# microstepper.net
KiCad netlist of a schematic drawn in EAGLE
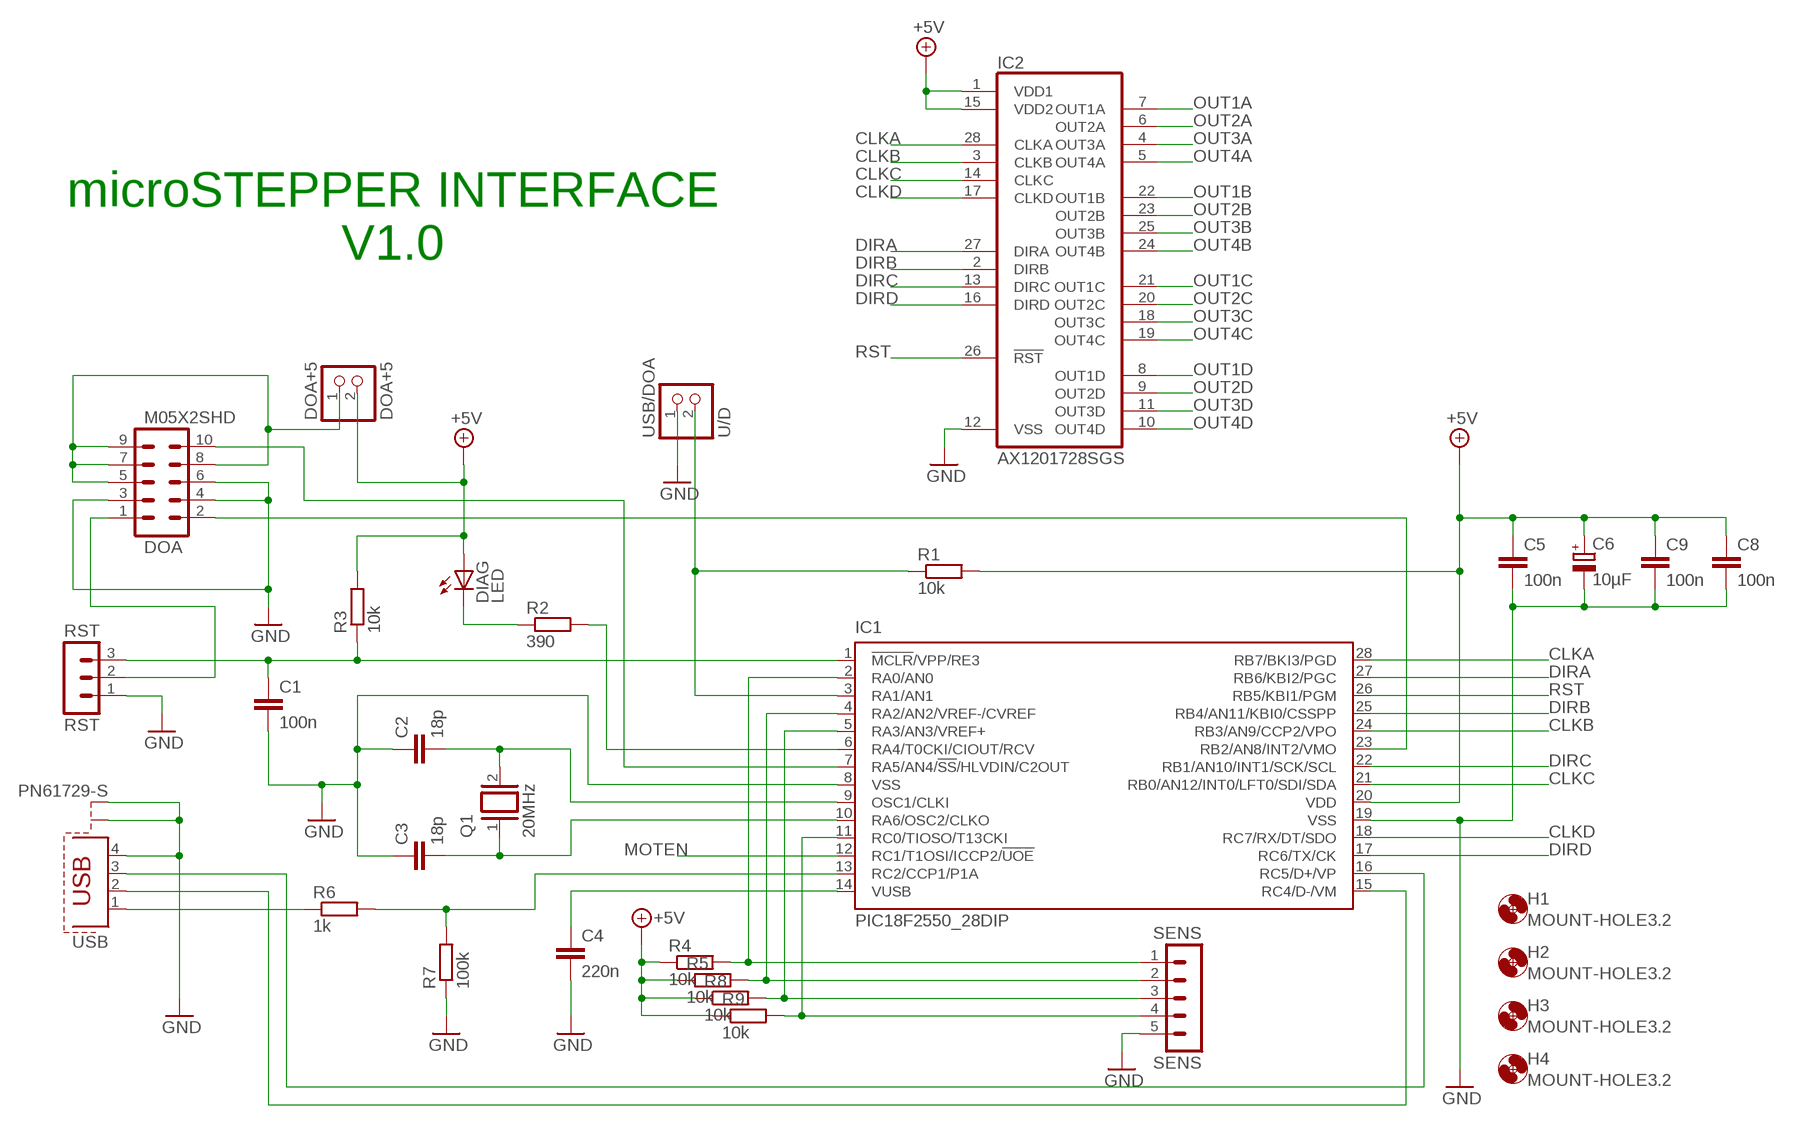
[diagram p0: schematic, sheet 1]
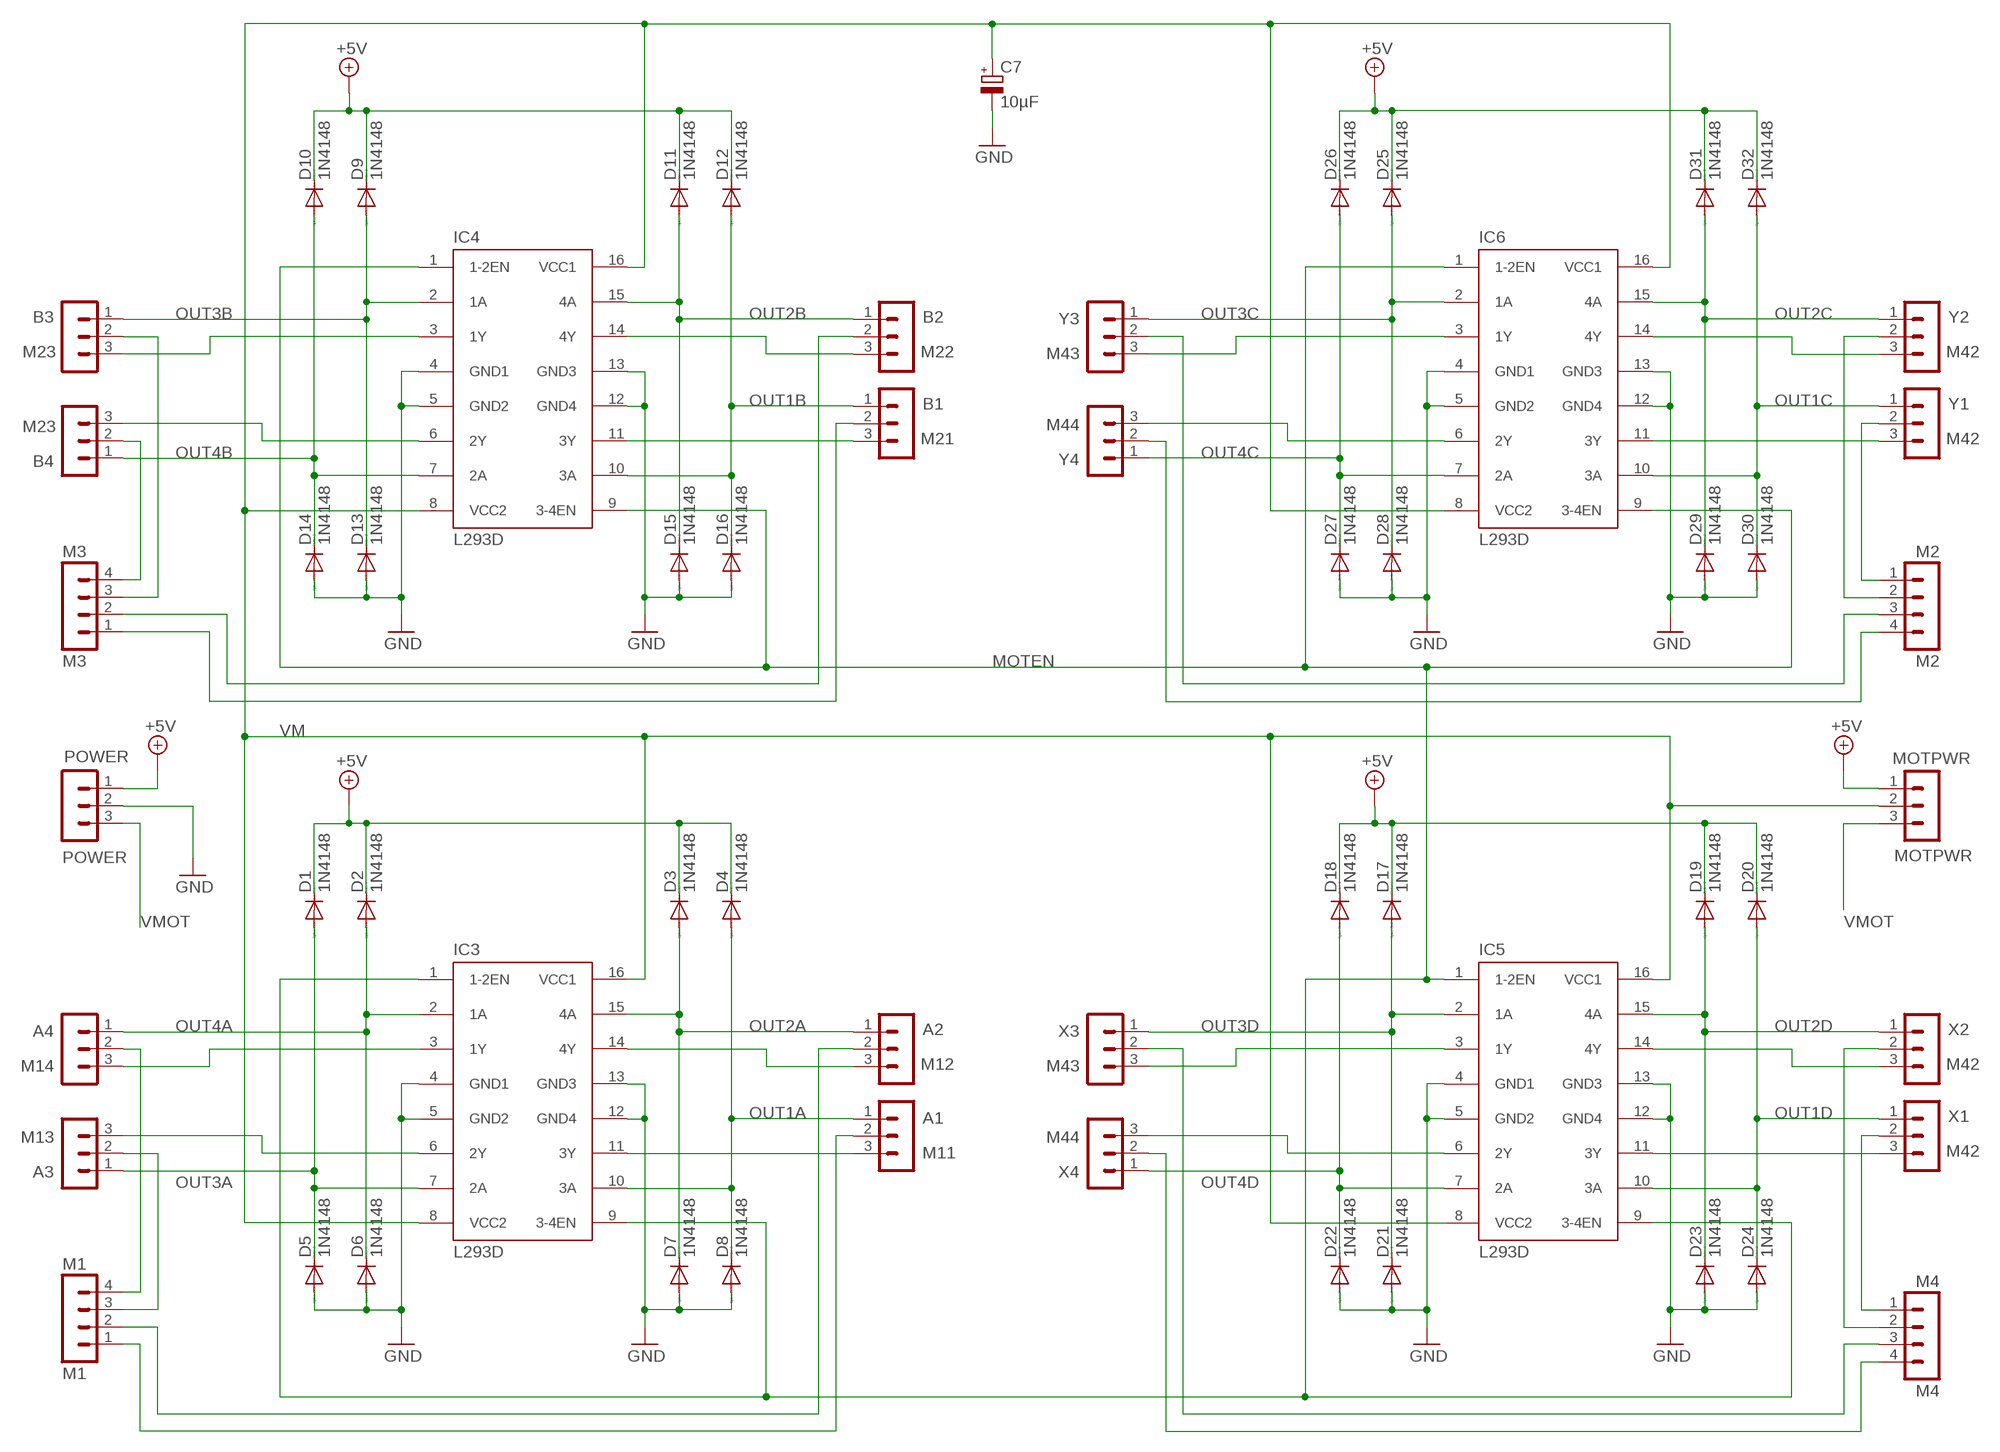
[diagram p1: schematic, sheet 2]
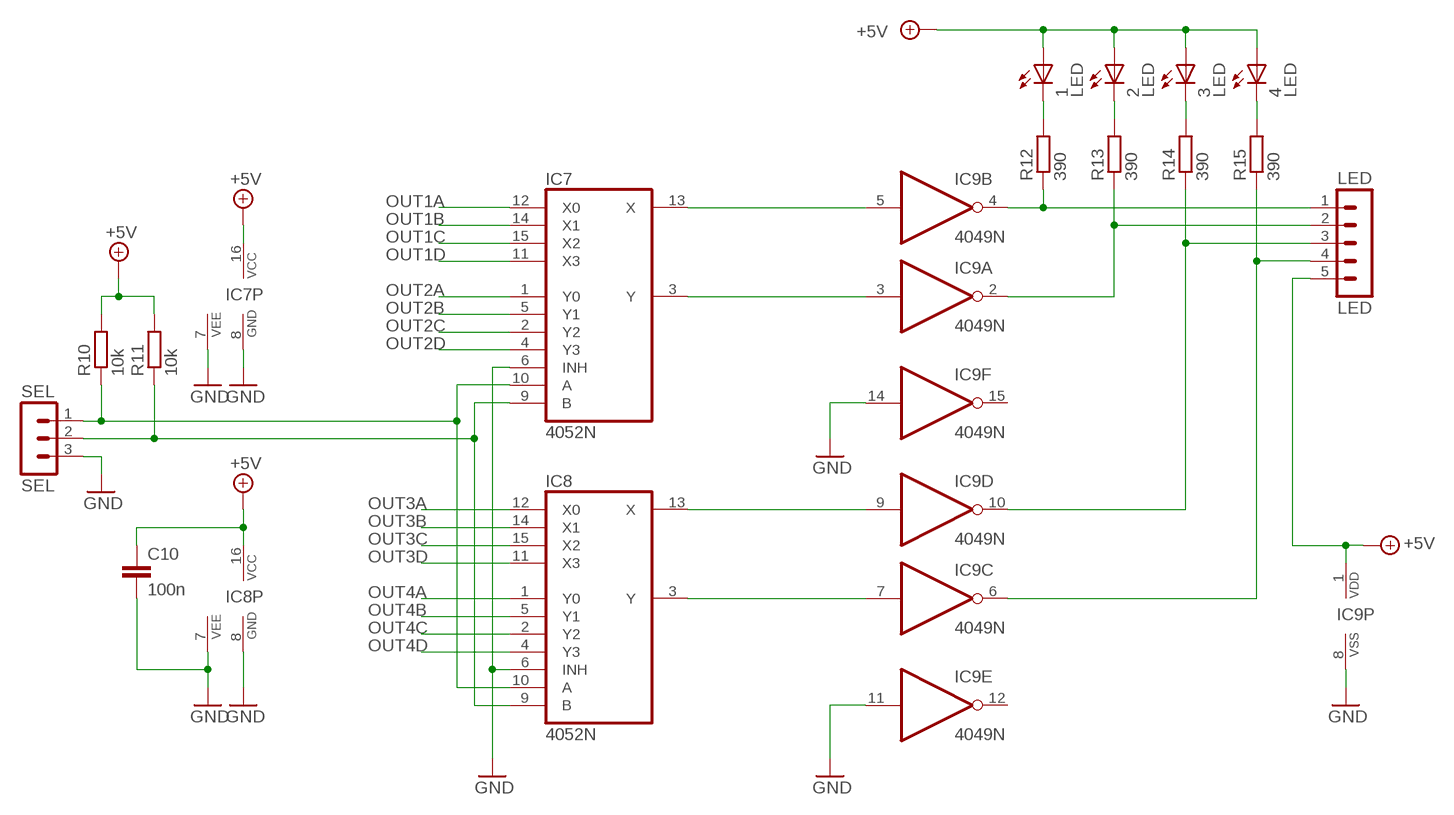
[diagram p2: schematic, sheet 3]

(export (version "E")
  (design (tool "Eeschema 10.0.6"))
  (components
    (comp (ref "C1")
      (value "100n")
      (footprint "eagle-import:C025-025X050")
      (libsource (lib "eagle-import") (part "C-EU025-025X050"))
    )
    (comp (ref "C2")
      (value "18p")
      (footprint "eagle-import:C025-025X050")
      (libsource (lib "eagle-import") (part "C-EU025-025X050"))
    )
    (comp (ref "C3")
      (value "18p")
      (footprint "eagle-import:C025-025X050")
      (libsource (lib "eagle-import") (part "C-EU025-025X050"))
    )
    (comp (ref "C4")
      (value "220n")
      (footprint "eagle-import:C5B3")
      (libsource (lib "eagle-import") (part "C5/3"))
    )
    (comp (ref "C5")
      (value "100n")
      (footprint "eagle-import:C025-025X050")
      (libsource (lib "eagle-import") (part "C-EU025-025X050"))
    )
    (comp (ref "C6")
      (value "10µF")
      (footprint "eagle-import:E2,5-5")
      (libsource (lib "eagle-import") (part "CPOL-EUE2.5-5"))
    )
    (comp (ref "C8")
      (value "100n")
      (footprint "eagle-import:C025-025X050")
      (libsource (lib "eagle-import") (part "C-EU025-025X050"))
    )
    (comp (ref "C9")
      (value "100n")
      (footprint "eagle-import:C025-025X050")
      (libsource (lib "eagle-import") (part "C-EU025-025X050"))
    )
    (comp (ref "DIAG")
      (value "LED")
      (footprint "eagle-import:LED3MM")
      (libsource (lib "eagle-import") (part "LED3MM"))
    )
    (comp (ref "DOA")
      (value "M05X2SHD")
      (footprint "eagle-import:2X5-SHROUDED")
      (libsource (lib "eagle-import") (part "M05X2SHD"))
    )
    (comp (ref "DOA+5")
      (value "DOA+5")
      (footprint "eagle-import:1X02")
      (libsource (lib "eagle-import") (part "PINHD-1X2"))
    )
    (comp (ref "H1")
      (value "MOUNT-HOLE3.2")
      (footprint "eagle-import:3,2")
      (libsource (lib "eagle-import") (part "MOUNT-HOLE3.2"))
    )
    (comp (ref "H2")
      (value "MOUNT-HOLE3.2")
      (footprint "eagle-import:3,2")
      (libsource (lib "eagle-import") (part "MOUNT-HOLE3.2"))
    )
    (comp (ref "H3")
      (value "MOUNT-HOLE3.2")
      (footprint "eagle-import:3,2")
      (libsource (lib "eagle-import") (part "MOUNT-HOLE3.2"))
    )
    (comp (ref "H4")
      (value "MOUNT-HOLE3.2")
      (footprint "eagle-import:3,2")
      (libsource (lib "eagle-import") (part "MOUNT-HOLE3.2"))
    )
    (comp (ref "IC1")
      (value "PIC18F2550_28DIP")
      (footprint "eagle-import:DIL28-3")
      (fields (field (name "MF") "MICROCHIP") (field (name "MPN") "PIC18F2550-I/SP"))
      (libsource (lib "eagle-import") (part "PIC18F2_28DIP550"))
    )
    (comp (ref "IC2")
      (value "AX1201728SGS")
      (footprint "eagle-import:SOP-28")
      (libsource (lib "eagle-import") (part "AX1201728SGS"))
    )
    (comp (ref "Q1")
      (value "20MHz")
      (footprint "eagle-import:QS")
      (libsource (lib "eagle-import") (part "XTAL/S"))
    )
    (comp (ref "R1")
      (value "10k")
      (footprint "eagle-import:0204_7")
      (libsource (lib "eagle-import") (part "R-EU_0204/7"))
    )
    (comp (ref "R2")
      (value "390")
      (footprint "eagle-import:0204_7")
      (libsource (lib "eagle-import") (part "R-EU_0204/7"))
    )
    (comp (ref "R3")
      (value "10k")
      (footprint "eagle-import:0204_7")
      (libsource (lib "eagle-import") (part "R-EU_0204/7"))
    )
    (comp (ref "R4")
      (value "10k")
      (footprint "eagle-import:0204_7")
      (libsource (lib "eagle-import") (part "R-EU_0204/7"))
    )
    (comp (ref "R5")
      (value "10k")
      (footprint "eagle-import:0204_7")
      (libsource (lib "eagle-import") (part "R-EU_0204/7"))
    )
    (comp (ref "R6")
      (value "1k")
      (footprint "eagle-import:0204_7")
      (libsource (lib "eagle-import") (part "R-EU_0204/7"))
    )
    (comp (ref "R7")
      (value "100k")
      (footprint "eagle-import:0204_7")
      (libsource (lib "eagle-import") (part "R-EU_0204/7"))
    )
    (comp (ref "R8")
      (value "10k")
      (footprint "eagle-import:0204_7")
      (libsource (lib "eagle-import") (part "R-EU_0204/7"))
    )
    (comp (ref "R9")
      (value "10k")
      (footprint "eagle-import:0204_7")
      (libsource (lib "eagle-import") (part "R-EU_0204/7"))
    )
    (comp (ref "RST")
      (value "RST")
      (footprint "eagle-import:MA03-1")
      (libsource (lib "eagle-import") (part "MA03-1"))
    )
    (comp (ref "SENS")
      (value "SENS")
      (footprint "eagle-import:MA05-1")
      (libsource (lib "eagle-import") (part "MA05-1"))
    )
    (comp (ref "USB")
      (value "PN61729-S")
      (footprint "eagle-import:PN61729-S")
      (libsource (lib "eagle-import") (part "PN61729-S"))
    )
    (comp (ref "USB/DOA")
      (value "U/D")
      (footprint "eagle-import:1X02")
      (libsource (lib "eagle-import") (part "PINHD-1X2"))
    )
    (comp (ref "1")
      (value "LED")
      (footprint "eagle-import:LED3MM")
      (libsource (lib "eagle-import") (part "LED3MM"))
    )
    (comp (ref "2")
      (value "LED")
      (footprint "eagle-import:LED3MM")
      (libsource (lib "eagle-import") (part "LED3MM"))
    )
    (comp (ref "3")
      (value "LED")
      (footprint "eagle-import:LED3MM")
      (libsource (lib "eagle-import") (part "LED3MM"))
    )
    (comp (ref "4")
      (value "LED")
      (footprint "eagle-import:LED3MM")
      (libsource (lib "eagle-import") (part "LED3MM"))
    )
    (comp (ref "C10")
      (value "100n")
      (footprint "eagle-import:C025-025X050")
      (libsource (lib "eagle-import") (part "C-EU025-025X050"))
    )
    (comp (ref "IC7")
      (value "4052N")
      (footprint "eagle-import:DIL16")
      (libsource (lib "eagle-import") (part "4052N"))
    )
    (comp (ref "IC8")
      (value "4052N")
      (footprint "eagle-import:DIL16")
      (libsource (lib "eagle-import") (part "4052N"))
    )
    (comp (ref "IC9")
      (value "4049N")
      (footprint "eagle-import:DIL16")
      (libsource (lib "eagle-import") (part "4049N"))
    )
    (comp (ref "LED")
      (value "LED")
      (footprint "eagle-import:MA05-1")
      (libsource (lib "eagle-import") (part "MA05-1"))
    )
    (comp (ref "R10")
      (value "10k")
      (footprint "eagle-import:0204_7")
      (libsource (lib "eagle-import") (part "R-EU_0204/7"))
    )
    (comp (ref "R11")
      (value "10k")
      (footprint "eagle-import:0204_7")
      (libsource (lib "eagle-import") (part "R-EU_0204/7"))
    )
    (comp (ref "R12")
      (value "390")
      (footprint "eagle-import:0204_7")
      (libsource (lib "eagle-import") (part "R-EU_0204/7"))
    )
    (comp (ref "R13")
      (value "390")
      (footprint "eagle-import:0204_7")
      (libsource (lib "eagle-import") (part "R-EU_0204/7"))
    )
    (comp (ref "R14")
      (value "390")
      (footprint "eagle-import:0204_7")
      (libsource (lib "eagle-import") (part "R-EU_0204/7"))
    )
    (comp (ref "R15")
      (value "390")
      (footprint "eagle-import:0204_7")
      (libsource (lib "eagle-import") (part "R-EU_0204/7"))
    )
    (comp (ref "SEL")
      (value "SEL")
      (footprint "eagle-import:MA03-1")
      (libsource (lib "eagle-import") (part "MA03-1"))
    )
    (comp (ref "A1")
      (value "M11")
      (footprint "eagle-import:MA03-1")
      (libsource (lib "eagle-import") (part "MA03-1"))
    )
    (comp (ref "A2")
      (value "M12")
      (footprint "eagle-import:MA03-1")
      (libsource (lib "eagle-import") (part "MA03-1"))
    )
    (comp (ref "A3")
      (value "M13")
      (footprint "eagle-import:MA03-1")
      (libsource (lib "eagle-import") (part "MA03-1"))
    )
    (comp (ref "A4")
      (value "M14")
      (footprint "eagle-import:MA03-1")
      (libsource (lib "eagle-import") (part "MA03-1"))
    )
    (comp (ref "B1")
      (value "M21")
      (footprint "eagle-import:MA03-1")
      (libsource (lib "eagle-import") (part "MA03-1"))
    )
    (comp (ref "B2")
      (value "M22")
      (footprint "eagle-import:MA03-1")
      (libsource (lib "eagle-import") (part "MA03-1"))
    )
    (comp (ref "B3")
      (value "M23")
      (footprint "eagle-import:MA03-1")
      (libsource (lib "eagle-import") (part "MA03-1"))
    )
    (comp (ref "B4")
      (value "M23")
      (footprint "eagle-import:MA03-1")
      (libsource (lib "eagle-import") (part "MA03-1"))
    )
    (comp (ref "C7")
      (value "10µF")
      (footprint "eagle-import:E2,5-5")
      (libsource (lib "eagle-import") (part "CPOL-EUE2.5-5"))
    )
    (comp (ref "D1")
      (value "1N4148")
      (footprint "eagle-import:DO35-7")
      (libsource (lib "eagle-import") (part "1N4148DO35-7"))
    )
    (comp (ref "D2")
      (value "1N4148")
      (footprint "eagle-import:DO35-7")
      (libsource (lib "eagle-import") (part "1N4148DO35-7"))
    )
    (comp (ref "D3")
      (value "1N4148")
      (footprint "eagle-import:DO35-7")
      (libsource (lib "eagle-import") (part "1N4148DO35-7"))
    )
    (comp (ref "D4")
      (value "1N4148")
      (footprint "eagle-import:DO35-7")
      (libsource (lib "eagle-import") (part "1N4148DO35-7"))
    )
    (comp (ref "D5")
      (value "1N4148")
      (footprint "eagle-import:DO35-7")
      (libsource (lib "eagle-import") (part "1N4148DO35-7"))
    )
    (comp (ref "D6")
      (value "1N4148")
      (footprint "eagle-import:DO35-7")
      (libsource (lib "eagle-import") (part "1N4148DO35-7"))
    )
    (comp (ref "D7")
      (value "1N4148")
      (footprint "eagle-import:DO35-7")
      (libsource (lib "eagle-import") (part "1N4148DO35-7"))
    )
    (comp (ref "D8")
      (value "1N4148")
      (footprint "eagle-import:DO35-7")
      (libsource (lib "eagle-import") (part "1N4148DO35-7"))
    )
    (comp (ref "D9")
      (value "1N4148")
      (footprint "eagle-import:DO35-7")
      (libsource (lib "eagle-import") (part "1N4148DO35-7"))
    )
    (comp (ref "D10")
      (value "1N4148")
      (footprint "eagle-import:DO35-7")
      (libsource (lib "eagle-import") (part "1N4148DO35-7"))
    )
    (comp (ref "D11")
      (value "1N4148")
      (footprint "eagle-import:DO35-7")
      (libsource (lib "eagle-import") (part "1N4148DO35-7"))
    )
    (comp (ref "D12")
      (value "1N4148")
      (footprint "eagle-import:DO35-7")
      (libsource (lib "eagle-import") (part "1N4148DO35-7"))
    )
    (comp (ref "D13")
      (value "1N4148")
      (footprint "eagle-import:DO35-7")
      (libsource (lib "eagle-import") (part "1N4148DO35-7"))
    )
    (comp (ref "D14")
      (value "1N4148")
      (footprint "eagle-import:DO35-7")
      (libsource (lib "eagle-import") (part "1N4148DO35-7"))
    )
    (comp (ref "D15")
      (value "1N4148")
      (footprint "eagle-import:DO35-7")
      (libsource (lib "eagle-import") (part "1N4148DO35-7"))
    )
    (comp (ref "D16")
      (value "1N4148")
      (footprint "eagle-import:DO35-7")
      (libsource (lib "eagle-import") (part "1N4148DO35-7"))
    )
    (comp (ref "D17")
      (value "1N4148")
      (footprint "eagle-import:DO35-7")
      (libsource (lib "eagle-import") (part "1N4148DO35-7"))
    )
    (comp (ref "D18")
      (value "1N4148")
      (footprint "eagle-import:DO35-7")
      (libsource (lib "eagle-import") (part "1N4148DO35-7"))
    )
    (comp (ref "D19")
      (value "1N4148")
      (footprint "eagle-import:DO35-7")
      (libsource (lib "eagle-import") (part "1N4148DO35-7"))
    )
    (comp (ref "D20")
      (value "1N4148")
      (footprint "eagle-import:DO35-7")
      (libsource (lib "eagle-import") (part "1N4148DO35-7"))
    )
    (comp (ref "D21")
      (value "1N4148")
      (footprint "eagle-import:DO35-7")
      (libsource (lib "eagle-import") (part "1N4148DO35-7"))
    )
    (comp (ref "D22")
      (value "1N4148")
      (footprint "eagle-import:DO35-7")
      (libsource (lib "eagle-import") (part "1N4148DO35-7"))
    )
    (comp (ref "D23")
      (value "1N4148")
      (footprint "eagle-import:DO35-7")
      (libsource (lib "eagle-import") (part "1N4148DO35-7"))
    )
    (comp (ref "D24")
      (value "1N4148")
      (footprint "eagle-import:DO35-7")
      (libsource (lib "eagle-import") (part "1N4148DO35-7"))
    )
    (comp (ref "D25")
      (value "1N4148")
      (footprint "eagle-import:DO35-7")
      (libsource (lib "eagle-import") (part "1N4148DO35-7"))
    )
    (comp (ref "D26")
      (value "1N4148")
      (footprint "eagle-import:DO35-7")
      (libsource (lib "eagle-import") (part "1N4148DO35-7"))
    )
    (comp (ref "D27")
      (value "1N4148")
      (footprint "eagle-import:DO35-7")
      (libsource (lib "eagle-import") (part "1N4148DO35-7"))
    )
    (comp (ref "D28")
      (value "1N4148")
      (footprint "eagle-import:DO35-7")
      (libsource (lib "eagle-import") (part "1N4148DO35-7"))
    )
    (comp (ref "D29")
      (value "1N4148")
      (footprint "eagle-import:DO35-7")
      (libsource (lib "eagle-import") (part "1N4148DO35-7"))
    )
    (comp (ref "D30")
      (value "1N4148")
      (footprint "eagle-import:DO35-7")
      (libsource (lib "eagle-import") (part "1N4148DO35-7"))
    )
    (comp (ref "D31")
      (value "1N4148")
      (footprint "eagle-import:DO35-7")
      (libsource (lib "eagle-import") (part "1N4148DO35-7"))
    )
    (comp (ref "D32")
      (value "1N4148")
      (footprint "eagle-import:DO35-7")
      (libsource (lib "eagle-import") (part "1N4148DO35-7"))
    )
    (comp (ref "IC3")
      (value "L293D")
      (footprint "eagle-import:DIL16")
      (libsource (lib "eagle-import") (part "L293D"))
    )
    (comp (ref "IC4")
      (value "L293D")
      (footprint "eagle-import:DIL16")
      (libsource (lib "eagle-import") (part "L293D"))
    )
    (comp (ref "IC5")
      (value "L293D")
      (footprint "eagle-import:DIL16")
      (libsource (lib "eagle-import") (part "L293D"))
    )
    (comp (ref "IC6")
      (value "L293D")
      (footprint "eagle-import:DIL16")
      (libsource (lib "eagle-import") (part "L293D"))
    )
    (comp (ref "M1")
      (value "M1")
      (footprint "eagle-import:MA04-1")
      (libsource (lib "eagle-import") (part "MA04-1"))
    )
    (comp (ref "M2")
      (value "M2")
      (footprint "eagle-import:MA04-1")
      (libsource (lib "eagle-import") (part "MA04-1"))
    )
    (comp (ref "M3")
      (value "M3")
      (footprint "eagle-import:MA04-1")
      (libsource (lib "eagle-import") (part "MA04-1"))
    )
    (comp (ref "M4")
      (value "M4")
      (footprint "eagle-import:MA04-1")
      (libsource (lib "eagle-import") (part "MA04-1"))
    )
    (comp (ref "MOTPWR")
      (value "MOTPWR")
      (footprint "eagle-import:MA03-1")
      (libsource (lib "eagle-import") (part "MA03-1"))
    )
    (comp (ref "POWER")
      (value "POWER")
      (footprint "eagle-import:MA03-1")
      (libsource (lib "eagle-import") (part "MA03-1"))
    )
    (comp (ref "X1")
      (value "M42")
      (footprint "eagle-import:MA03-1")
      (libsource (lib "eagle-import") (part "MA03-1"))
    )
    (comp (ref "X2")
      (value "M42")
      (footprint "eagle-import:MA03-1")
      (libsource (lib "eagle-import") (part "MA03-1"))
    )
    (comp (ref "X3")
      (value "M43")
      (footprint "eagle-import:MA03-1")
      (libsource (lib "eagle-import") (part "MA03-1"))
    )
    (comp (ref "X4")
      (value "M44")
      (footprint "eagle-import:MA03-1")
      (libsource (lib "eagle-import") (part "MA03-1"))
    )
    (comp (ref "Y1")
      (value "M42")
      (footprint "eagle-import:MA03-1")
      (libsource (lib "eagle-import") (part "MA03-1"))
    )
    (comp (ref "Y2")
      (value "M42")
      (footprint "eagle-import:MA03-1")
      (libsource (lib "eagle-import") (part "MA03-1"))
    )
    (comp (ref "Y3")
      (value "M43")
      (footprint "eagle-import:MA03-1")
      (libsource (lib "eagle-import") (part "MA03-1"))
    )
    (comp (ref "Y4")
      (value "M44")
      (footprint "eagle-import:MA03-1")
      (libsource (lib "eagle-import") (part "MA03-1"))
    )
  )
  (nets
    (net (code "1") (name "+5V") (class "Default")
      (node (ref "1") (pin "A") (pinfunction "A_A") (pintype "passive"))
      (node (ref "2") (pin "A") (pinfunction "A_A") (pintype "passive"))
      (node (ref "3") (pin "A") (pinfunction "A_A") (pintype "passive"))
      (node (ref "4") (pin "A") (pinfunction "A_A") (pintype "passive"))
      (node (ref "C10") (pin "1") (pinfunction "1_1") (pintype "passive"))
      (node (ref "C5") (pin "1") (pinfunction "1_1") (pintype "passive"))
      (node (ref "C6") (pin "+") (pinfunction "+_+") (pintype "passive"))
      (node (ref "C8") (pin "1") (pinfunction "1_1") (pintype "passive"))
      (node (ref "C9") (pin "1") (pinfunction "1_1") (pintype "passive"))
      (node (ref "D1") (pin "C") (pinfunction "C_C") (pintype "passive"))
      (node (ref "D10") (pin "C") (pinfunction "C_C") (pintype "passive"))
      (node (ref "D11") (pin "C") (pinfunction "C_C") (pintype "passive"))
      (node (ref "D12") (pin "C") (pinfunction "C_C") (pintype "passive"))
      (node (ref "D17") (pin "C") (pinfunction "C_C") (pintype "passive"))
      (node (ref "D18") (pin "C") (pinfunction "C_C") (pintype "passive"))
      (node (ref "D19") (pin "C") (pinfunction "C_C") (pintype "passive"))
      (node (ref "D2") (pin "C") (pinfunction "C_C") (pintype "passive"))
      (node (ref "D20") (pin "C") (pinfunction "C_C") (pintype "passive"))
      (node (ref "D25") (pin "C") (pinfunction "C_C") (pintype "passive"))
      (node (ref "D26") (pin "C") (pinfunction "C_C") (pintype "passive"))
      (node (ref "D3") (pin "C") (pinfunction "C_C") (pintype "passive"))
      (node (ref "D31") (pin "C") (pinfunction "C_C") (pintype "passive"))
      (node (ref "D32") (pin "C") (pinfunction "C_C") (pintype "passive"))
      (node (ref "D4") (pin "C") (pinfunction "C_C") (pintype "passive"))
      (node (ref "D9") (pin "C") (pinfunction "C_C") (pintype "passive"))
      (node (ref "DIAG") (pin "A") (pinfunction "A_A") (pintype "passive"))
      (node (ref "DOA+5") (pin "2") (pinfunction "2_2") (pintype "passive"))
      (node (ref "IC1") (pin "20") (pinfunction "VDD_20") (pintype "power_in"))
      (node (ref "IC2") (pin "1") (pinfunction "VDD1_1") (pintype "power_in"))
      (node (ref "IC2") (pin "15") (pinfunction "VDD2_15") (pintype "power_in"))
      (node (ref "IC7") (pin "16") (pinfunction "VCC_16") (pintype "power_in"))
      (node (ref "IC8") (pin "16") (pinfunction "VCC_16") (pintype "power_in"))
      (node (ref "IC9") (pin "1") (pinfunction "VDD_1") (pintype "power_in"))
      (node (ref "LED") (pin "5") (pinfunction "5_5") (pintype "passive"))
      (node (ref "MOTPWR") (pin "1") (pinfunction "1_1") (pintype "passive"))
      (node (ref "POWER") (pin "1") (pinfunction "1_1") (pintype "passive"))
      (node (ref "R1") (pin "2") (pinfunction "2_2") (pintype "passive"))
      (node (ref "R10") (pin "2") (pinfunction "2_2") (pintype "passive"))
      (node (ref "R11") (pin "2") (pinfunction "2_2") (pintype "passive"))
      (node (ref "R3") (pin "2") (pinfunction "2_2") (pintype "passive"))
      (node (ref "R4") (pin "1") (pinfunction "1_1") (pintype "passive"))
      (node (ref "R5") (pin "1") (pinfunction "1_1") (pintype "passive"))
      (node (ref "R8") (pin "1") (pinfunction "1_1") (pintype "passive"))
      (node (ref "R9") (pin "1") (pinfunction "1_1") (pintype "passive"))
    )
    (net (code "2") (name "CLKA") (class "Default")
      (node (ref "IC1") (pin "28") (pinfunction "RB7/BKI3/PGD_28") (pintype "bidirectional"))
      (node (ref "IC2") (pin "28") (pinfunction "CLKA_28") (pintype "input"))
    )
    (net (code "3") (name "CLKB") (class "Default")
      (node (ref "IC1") (pin "24") (pinfunction "RB3/AN9/CCP2/VPO_24") (pintype "bidirectional"))
      (node (ref "IC2") (pin "3") (pinfunction "CLKB_3") (pintype "input"))
    )
    (net (code "4") (name "CLKC") (class "Default")
      (node (ref "IC1") (pin "21") (pinfunction "RB0/AN12/INT0/LFT0/SDI/SDA_21") (pintype "bidirectional"))
      (node (ref "IC2") (pin "14") (pinfunction "CLKC_14") (pintype "input"))
    )
    (net (code "5") (name "CLKD") (class "Default")
      (node (ref "IC1") (pin "18") (pinfunction "RC7/RX/DT/SDO_18") (pintype "bidirectional"))
      (node (ref "IC2") (pin "17") (pinfunction "CLKD_17") (pintype "input"))
    )
    (net (code "6") (name "DIRA") (class "Default")
      (node (ref "IC1") (pin "27") (pinfunction "RB6/KBI2/PGC_27") (pintype "bidirectional"))
      (node (ref "IC2") (pin "27") (pinfunction "DIRA_27") (pintype "input"))
    )
    (net (code "7") (name "DIRB") (class "Default")
      (node (ref "IC1") (pin "25") (pinfunction "RB4/AN11/KBI0/CSSPP_25") (pintype "bidirectional"))
      (node (ref "IC2") (pin "2") (pinfunction "DIRB_2") (pintype "input"))
    )
    (net (code "8") (name "DIRC") (class "Default")
      (node (ref "IC1") (pin "22") (pinfunction "RB1/AN10/INT1/SCK/SCL_22") (pintype "bidirectional"))
      (node (ref "IC2") (pin "13") (pinfunction "DIRC_13") (pintype "input"))
    )
    (net (code "9") (name "DIRD") (class "Default")
      (node (ref "IC1") (pin "17") (pinfunction "RC6/TX/CK_17") (pintype "bidirectional"))
      (node (ref "IC2") (pin "16") (pinfunction "DIRD_16") (pintype "input"))
    )
    (net (code "10") (name "GND") (class "Default")
      (node (ref "C1") (pin "2") (pinfunction "2_2") (pintype "passive"))
      (node (ref "C10") (pin "2") (pinfunction "2_2") (pintype "passive"))
      (node (ref "C2") (pin "1") (pinfunction "1_1") (pintype "passive"))
      (node (ref "C3") (pin "1") (pinfunction "1_1") (pintype "passive"))
      (node (ref "C4") (pin "2") (pinfunction "2_2") (pintype "passive"))
      (node (ref "C5") (pin "2") (pinfunction "2_2") (pintype "passive"))
      (node (ref "C6") (pin "-") (pinfunction "-_-") (pintype "passive"))
      (node (ref "C7") (pin "-") (pinfunction "-_-") (pintype "passive"))
      (node (ref "C8") (pin "2") (pinfunction "2_2") (pintype "passive"))
      (node (ref "C9") (pin "2") (pinfunction "2_2") (pintype "passive"))
      (node (ref "D13") (pin "A") (pinfunction "A_A") (pintype "passive"))
      (node (ref "D14") (pin "A") (pinfunction "A_A") (pintype "passive"))
      (node (ref "D15") (pin "A") (pinfunction "A_A") (pintype "passive"))
      (node (ref "D16") (pin "A") (pinfunction "A_A") (pintype "passive"))
      (node (ref "D21") (pin "A") (pinfunction "A_A") (pintype "passive"))
      (node (ref "D22") (pin "A") (pinfunction "A_A") (pintype "passive"))
      (node (ref "D23") (pin "A") (pinfunction "A_A") (pintype "passive"))
      (node (ref "D24") (pin "A") (pinfunction "A_A") (pintype "passive"))
      (node (ref "D27") (pin "A") (pinfunction "A_A") (pintype "passive"))
      (node (ref "D28") (pin "A") (pinfunction "A_A") (pintype "passive"))
      (node (ref "D29") (pin "A") (pinfunction "A_A") (pintype "passive"))
      (node (ref "D30") (pin "A") (pinfunction "A_A") (pintype "passive"))
      (node (ref "D5") (pin "A") (pinfunction "A_A") (pintype "passive"))
      (node (ref "D6") (pin "A") (pinfunction "A_A") (pintype "passive"))
      (node (ref "D7") (pin "A") (pinfunction "A_A") (pintype "passive"))
      (node (ref "D8") (pin "A") (pinfunction "A_A") (pintype "passive"))
      (node (ref "DOA") (pin "3") (pinfunction "3_3") (pintype "passive"))
      (node (ref "DOA") (pin "4") (pinfunction "4_4") (pintype "passive"))
      (node (ref "DOA") (pin "6") (pinfunction "6_6") (pintype "passive"))
      (node (ref "IC1") (pin "19") (pinfunction "VSS_19") (pintype "power_in"))
      (node (ref "IC1") (pin "8") (pinfunction "VSS_8") (pintype "power_in"))
      (node (ref "IC2") (pin "12") (pinfunction "VSS_12") (pintype "power_in"))
      (node (ref "IC3") (pin "12") (pinfunction "GND4_12") (pintype "power_in"))
      (node (ref "IC3") (pin "13") (pinfunction "GND3_13") (pintype "power_in"))
      (node (ref "IC3") (pin "4") (pinfunction "GND1_4") (pintype "power_in"))
      (node (ref "IC3") (pin "5") (pinfunction "GND2_5") (pintype "power_in"))
      (node (ref "IC4") (pin "12") (pinfunction "GND4_12") (pintype "power_in"))
      (node (ref "IC4") (pin "13") (pinfunction "GND3_13") (pintype "power_in"))
      (node (ref "IC4") (pin "4") (pinfunction "GND1_4") (pintype "power_in"))
      (node (ref "IC4") (pin "5") (pinfunction "GND2_5") (pintype "power_in"))
      (node (ref "IC5") (pin "12") (pinfunction "GND4_12") (pintype "power_in"))
      (node (ref "IC5") (pin "13") (pinfunction "GND3_13") (pintype "power_in"))
      (node (ref "IC5") (pin "4") (pinfunction "GND1_4") (pintype "power_in"))
      (node (ref "IC5") (pin "5") (pinfunction "GND2_5") (pintype "power_in"))
      (node (ref "IC6") (pin "12") (pinfunction "GND4_12") (pintype "power_in"))
      (node (ref "IC6") (pin "13") (pinfunction "GND3_13") (pintype "power_in"))
      (node (ref "IC6") (pin "4") (pinfunction "GND1_4") (pintype "power_in"))
      (node (ref "IC6") (pin "5") (pinfunction "GND2_5") (pintype "power_in"))
      (node (ref "IC7") (pin "6") (pinfunction "INH_6") (pintype "input"))
      (node (ref "IC7") (pin "7") (pinfunction "VEE_7") (pintype "power_in"))
      (node (ref "IC7") (pin "8") (pinfunction "GND_8") (pintype "power_in"))
      (node (ref "IC8") (pin "6") (pinfunction "INH_6") (pintype "input"))
      (node (ref "IC8") (pin "7") (pinfunction "VEE_7") (pintype "power_in"))
      (node (ref "IC8") (pin "8") (pinfunction "GND_8") (pintype "power_in"))
      (node (ref "IC9") (pin "11") (pinfunction "I_11") (pintype "input"))
      (node (ref "IC9") (pin "14") (pinfunction "I_14") (pintype "input"))
      (node (ref "IC9") (pin "8") (pinfunction "VSS_8") (pintype "power_in"))
      (node (ref "POWER") (pin "2") (pinfunction "2_2") (pintype "passive"))
      (node (ref "R7") (pin "1") (pinfunction "1_1") (pintype "passive"))
      (node (ref "RST") (pin "1") (pinfunction "1_1") (pintype "passive"))
      (node (ref "SEL") (pin "3") (pinfunction "3_3") (pintype "passive"))
      (node (ref "SENS") (pin "5") (pinfunction "5_5") (pintype "passive"))
      (node (ref "USB") (pin "4") (pinfunction "4_4") (pintype "passive"))
      (node (ref "USB") (pin "S1") (pinfunction "S1_S1") (pintype "passive"))
      (node (ref "USB") (pin "S2") (pinfunction "S2_S2") (pintype "passive"))
      (node (ref "USB/DOA") (pin "1") (pinfunction "1_1") (pintype "passive"))
    )
    (net (code "11") (name "MOTEN") (class "Default")
      (node (ref "IC1") (pin "12") (pinfunction "RC1/T1OSI/ICCP2/~{UOE}_12") (pintype "bidirectional"))
      (node (ref "IC3") (pin "1") (pinfunction "1-2EN_1") (pintype "input"))
      (node (ref "IC3") (pin "9") (pinfunction "3-4EN_9") (pintype "input"))
      (node (ref "IC4") (pin "1") (pinfunction "1-2EN_1") (pintype "input"))
      (node (ref "IC4") (pin "9") (pinfunction "3-4EN_9") (pintype "input"))
      (node (ref "IC5") (pin "1") (pinfunction "1-2EN_1") (pintype "input"))
      (node (ref "IC5") (pin "9") (pinfunction "3-4EN_9") (pintype "input"))
      (node (ref "IC6") (pin "1") (pinfunction "1-2EN_1") (pintype "input"))
      (node (ref "IC6") (pin "9") (pinfunction "3-4EN_9") (pintype "input"))
    )
    (net (code "12") (name "Net-(1-C)") (class "Default")
      (node (ref "1") (pin "K") (pinfunction "C_K") (pintype "passive"))
      (node (ref "R12") (pin "2") (pinfunction "2_2") (pintype "passive"))
    )
    (net (code "13") (name "Net-(2-C)") (class "Default")
      (node (ref "2") (pin "K") (pinfunction "C_K") (pintype "passive"))
      (node (ref "R13") (pin "2") (pinfunction "2_2") (pintype "passive"))
    )
    (net (code "14") (name "Net-(3-C)") (class "Default")
      (node (ref "3") (pin "K") (pinfunction "C_K") (pintype "passive"))
      (node (ref "R14") (pin "2") (pinfunction "2_2") (pintype "passive"))
    )
    (net (code "15") (name "Net-(4-C)") (class "Default")
      (node (ref "4") (pin "K") (pinfunction "C_K") (pintype "passive"))
      (node (ref "R15") (pin "2") (pinfunction "2_2") (pintype "passive"))
    )
    (net (code "16") (name "Net-(A1-Pad2)") (class "Default")
      (node (ref "A1") (pin "2") (pinfunction "2_2") (pintype "passive"))
      (node (ref "M1") (pin "1") (pinfunction "1_1") (pintype "passive"))
    )
    (net (code "17") (name "Net-(A2-Pad2)") (class "Default")
      (node (ref "A2") (pin "2") (pinfunction "2_2") (pintype "passive"))
      (node (ref "M1") (pin "2") (pinfunction "2_2") (pintype "passive"))
    )
    (net (code "18") (name "Net-(A3-Pad2)") (class "Default")
      (node (ref "A3") (pin "2") (pinfunction "2_2") (pintype "passive"))
      (node (ref "M1") (pin "3") (pinfunction "3_3") (pintype "passive"))
    )
    (net (code "19") (name "Net-(A4-Pad2)") (class "Default")
      (node (ref "A4") (pin "2") (pinfunction "2_2") (pintype "passive"))
      (node (ref "M1") (pin "4") (pinfunction "4_4") (pintype "passive"))
    )
    (net (code "20") (name "Net-(B1-Pad2)") (class "Default")
      (node (ref "B1") (pin "2") (pinfunction "2_2") (pintype "passive"))
      (node (ref "M3") (pin "1") (pinfunction "1_1") (pintype "passive"))
    )
    (net (code "21") (name "Net-(B2-Pad2)") (class "Default")
      (node (ref "B2") (pin "2") (pinfunction "2_2") (pintype "passive"))
      (node (ref "M3") (pin "2") (pinfunction "2_2") (pintype "passive"))
    )
    (net (code "22") (name "Net-(B3-Pad2)") (class "Default")
      (node (ref "B3") (pin "2") (pinfunction "2_2") (pintype "passive"))
      (node (ref "M3") (pin "3") (pinfunction "3_3") (pintype "passive"))
    )
    (net (code "23") (name "Net-(B4-Pad2)") (class "Default")
      (node (ref "B4") (pin "2") (pinfunction "2_2") (pintype "passive"))
      (node (ref "M3") (pin "4") (pinfunction "4_4") (pintype "passive"))
    )
    (net (code "24") (name "Net-(DIAG-C)") (class "Default")
      (node (ref "DIAG") (pin "K") (pinfunction "C_K") (pintype "passive"))
      (node (ref "R2") (pin "1") (pinfunction "1_1") (pintype "passive"))
    )
    (net (code "25") (name "Net-(DOA+5-Pad1)") (class "Default")
      (node (ref "DOA") (pin "5") (pinfunction "5_5") (pintype "passive"))
      (node (ref "DOA") (pin "7") (pinfunction "7_7") (pintype "passive"))
      (node (ref "DOA") (pin "8") (pinfunction "8_8") (pintype "passive"))
      (node (ref "DOA") (pin "9") (pinfunction "9_9") (pintype "passive"))
      (node (ref "DOA+5") (pin "1") (pinfunction "1_1") (pintype "passive"))
    )
    (net (code "26") (name "Net-(DOA-Pad1)") (class "Default")
      (node (ref "DOA") (pin "1") (pinfunction "1_1") (pintype "passive"))
      (node (ref "RST") (pin "2") (pinfunction "2_2") (pintype "passive"))
    )
    (net (code "27") (name "Net-(IC1-OSC1{slash}CLKI)") (class "Default")
      (node (ref "C2") (pin "2") (pinfunction "2_2") (pintype "passive"))
      (node (ref "IC1") (pin "9") (pinfunction "OSC1/CLKI_9") (pintype "input"))
      (node (ref "Q1") (pin "2") (pinfunction "2_2") (pintype "passive"))
    )
    (net (code "28") (name "Net-(IC1-RA0{slash}AN0)") (class "Default")
      (node (ref "IC1") (pin "2") (pinfunction "RA0/AN0_2") (pintype "bidirectional"))
      (node (ref "R4") (pin "2") (pinfunction "2_2") (pintype "passive"))
      (node (ref "SENS") (pin "1") (pinfunction "1_1") (pintype "passive"))
    )
    (net (code "29") (name "Net-(IC1-RA1{slash}AN1)") (class "Default")
      (node (ref "IC1") (pin "3") (pinfunction "RA1/AN1_3") (pintype "bidirectional"))
      (node (ref "R1") (pin "1") (pinfunction "1_1") (pintype "passive"))
      (node (ref "USB/DOA") (pin "2") (pinfunction "2_2") (pintype "passive"))
    )
    (net (code "30") (name "Net-(IC1-RA2{slash}AN2{slash}VREF-{slash}CVREF)") (class "Default")
      (node (ref "IC1") (pin "4") (pinfunction "RA2/AN2/VREF-/CVREF_4") (pintype "bidirectional"))
      (node (ref "R5") (pin "2") (pinfunction "2_2") (pintype "passive"))
      (node (ref "SENS") (pin "2") (pinfunction "2_2") (pintype "passive"))
    )
    (net (code "31") (name "Net-(IC1-RA3{slash}AN3{slash}VREF+)") (class "Default")
      (node (ref "IC1") (pin "5") (pinfunction "RA3/AN3/VREF+_5") (pintype "bidirectional"))
      (node (ref "R8") (pin "2") (pinfunction "2_2") (pintype "passive"))
      (node (ref "SENS") (pin "3") (pinfunction "3_3") (pintype "passive"))
    )
    (net (code "32") (name "Net-(IC1-RA4{slash}T0CKI{slash}CIOUT{slash}RCV)") (class "Default")
      (node (ref "IC1") (pin "6") (pinfunction "RA4/T0CKI/CIOUT/RCV_6") (pintype "bidirectional"))
      (node (ref "R2") (pin "2") (pinfunction "2_2") (pintype "passive"))
    )
    (net (code "33") (name "Net-(IC1-RA5{slash}AN4{slash}~{SS}{slash}HLVDIN{slash}C2OUT)") (class "Default")
      (node (ref "DOA") (pin "10") (pinfunction "10_10") (pintype "passive"))
      (node (ref "IC1") (pin "7") (pinfunction "RA5/AN4/~{SS}/HLVDIN/C2OUT_7") (pintype "bidirectional"))
    )
    (net (code "34") (name "Net-(IC1-RA6{slash}OSC2{slash}CLKO)") (class "Default")
      (node (ref "C3") (pin "2") (pinfunction "2_2") (pintype "passive"))
      (node (ref "IC1") (pin "10") (pinfunction "RA6/OSC2/CLKO_10") (pintype "output"))
      (node (ref "Q1") (pin "1") (pinfunction "1_1") (pintype "passive"))
    )
    (net (code "35") (name "Net-(IC1-RB2{slash}AN8{slash}INT2{slash}VMO)") (class "Default")
      (node (ref "DOA") (pin "2") (pinfunction "2_2") (pintype "passive"))
      (node (ref "IC1") (pin "23") (pinfunction "RB2/AN8/INT2/VMO_23") (pintype "bidirectional"))
    )
    (net (code "36") (name "Net-(IC1-RC0{slash}TIOSO{slash}T13CKI)") (class "Default")
      (node (ref "IC1") (pin "11") (pinfunction "RC0/TIOSO/T13CKI_11") (pintype "bidirectional"))
      (node (ref "R9") (pin "2") (pinfunction "2_2") (pintype "passive"))
      (node (ref "SENS") (pin "4") (pinfunction "4_4") (pintype "passive"))
    )
    (net (code "37") (name "Net-(IC1-RC2{slash}CCP1{slash}P1A)") (class "Default")
      (node (ref "IC1") (pin "13") (pinfunction "RC2/CCP1/P1A_13") (pintype "bidirectional"))
      (node (ref "R6") (pin "2") (pinfunction "2_2") (pintype "passive"))
      (node (ref "R7") (pin "2") (pinfunction "2_2") (pintype "passive"))
    )
    (net (code "38") (name "Net-(IC1-RC4{slash}D-{slash}VM)") (class "Default")
      (node (ref "IC1") (pin "15") (pinfunction "RC4/D-/VM_15") (pintype "bidirectional"))
      (node (ref "USB") (pin "2") (pinfunction "2_2") (pintype "passive"))
    )
    (net (code "39") (name "Net-(IC1-RC5{slash}D+{slash}VP)") (class "Default")
      (node (ref "IC1") (pin "16") (pinfunction "RC5/D+/VP_16") (pintype "bidirectional"))
      (node (ref "USB") (pin "3") (pinfunction "3_3") (pintype "passive"))
    )
    (net (code "40") (name "Net-(IC1-VUSB)") (class "Default")
      (node (ref "C4") (pin "1") (pinfunction "1_1") (pintype "passive"))
      (node (ref "IC1") (pin "14") (pinfunction "VUSB_14") (pintype "bidirectional"))
    )
    (net (code "41") (name "Net-(IC1-~{MCLR}{slash}VPP{slash}RE3)") (class "Default")
      (node (ref "C1") (pin "1") (pinfunction "1_1") (pintype "passive"))
      (node (ref "IC1") (pin "1") (pinfunction "~{MCLR}/VPP/RE3_1") (pintype "input"))
      (node (ref "R3") (pin "1") (pinfunction "1_1") (pintype "passive"))
      (node (ref "RST") (pin "3") (pinfunction "3_3") (pintype "passive"))
    )
    (net (code "42") (name "Net-(IC3-1Y)") (class "Default")
      (node (ref "A4") (pin "3") (pinfunction "3_3") (pintype "passive"))
      (node (ref "IC3") (pin "3") (pinfunction "1Y_3") (pintype "output"))
    )
    (net (code "43") (name "Net-(IC3-2Y)") (class "Default")
      (node (ref "A3") (pin "3") (pinfunction "3_3") (pintype "passive"))
      (node (ref "IC3") (pin "6") (pinfunction "2Y_6") (pintype "output"))
    )
    (net (code "44") (name "Net-(IC3-3Y)") (class "Default")
      (node (ref "A1") (pin "3") (pinfunction "3_3") (pintype "passive"))
      (node (ref "IC3") (pin "11") (pinfunction "3Y_11") (pintype "output"))
    )
    (net (code "45") (name "Net-(IC3-4Y)") (class "Default")
      (node (ref "A2") (pin "3") (pinfunction "3_3") (pintype "passive"))
      (node (ref "IC3") (pin "14") (pinfunction "4Y_14") (pintype "output"))
    )
    (net (code "46") (name "Net-(IC4-1Y)") (class "Default")
      (node (ref "B3") (pin "3") (pinfunction "3_3") (pintype "passive"))
      (node (ref "IC4") (pin "3") (pinfunction "1Y_3") (pintype "output"))
    )
    (net (code "47") (name "Net-(IC4-2Y)") (class "Default")
      (node (ref "B4") (pin "3") (pinfunction "3_3") (pintype "passive"))
      (node (ref "IC4") (pin "6") (pinfunction "2Y_6") (pintype "output"))
    )
    (net (code "48") (name "Net-(IC4-3Y)") (class "Default")
      (node (ref "B1") (pin "3") (pinfunction "3_3") (pintype "passive"))
      (node (ref "IC4") (pin "11") (pinfunction "3Y_11") (pintype "output"))
    )
    (net (code "49") (name "Net-(IC4-4Y)") (class "Default")
      (node (ref "B2") (pin "3") (pinfunction "3_3") (pintype "passive"))
      (node (ref "IC4") (pin "14") (pinfunction "4Y_14") (pintype "output"))
    )
    (net (code "50") (name "Net-(IC5-1Y)") (class "Default")
      (node (ref "IC5") (pin "3") (pinfunction "1Y_3") (pintype "output"))
      (node (ref "X3") (pin "3") (pinfunction "3_3") (pintype "passive"))
    )
    (net (code "51") (name "Net-(IC5-2Y)") (class "Default")
      (node (ref "IC5") (pin "6") (pinfunction "2Y_6") (pintype "output"))
      (node (ref "X4") (pin "3") (pinfunction "3_3") (pintype "passive"))
    )
    (net (code "52") (name "Net-(IC5-3Y)") (class "Default")
      (node (ref "IC5") (pin "11") (pinfunction "3Y_11") (pintype "output"))
      (node (ref "X1") (pin "3") (pinfunction "3_3") (pintype "passive"))
    )
    (net (code "53") (name "Net-(IC5-4Y)") (class "Default")
      (node (ref "IC5") (pin "14") (pinfunction "4Y_14") (pintype "output"))
      (node (ref "X2") (pin "3") (pinfunction "3_3") (pintype "passive"))
    )
    (net (code "54") (name "Net-(IC6-1Y)") (class "Default")
      (node (ref "IC6") (pin "3") (pinfunction "1Y_3") (pintype "output"))
      (node (ref "Y3") (pin "3") (pinfunction "3_3") (pintype "passive"))
    )
    (net (code "55") (name "Net-(IC6-2Y)") (class "Default")
      (node (ref "IC6") (pin "6") (pinfunction "2Y_6") (pintype "output"))
      (node (ref "Y4") (pin "3") (pinfunction "3_3") (pintype "passive"))
    )
    (net (code "56") (name "Net-(IC6-3Y)") (class "Default")
      (node (ref "IC6") (pin "11") (pinfunction "3Y_11") (pintype "output"))
      (node (ref "Y1") (pin "3") (pinfunction "3_3") (pintype "passive"))
    )
    (net (code "57") (name "Net-(IC6-4Y)") (class "Default")
      (node (ref "IC6") (pin "14") (pinfunction "4Y_14") (pintype "output"))
      (node (ref "Y2") (pin "3") (pinfunction "3_3") (pintype "passive"))
    )
    (net (code "58") (name "Net-(IC7A-A)") (class "Default")
      (node (ref "IC7") (pin "10") (pinfunction "A_10") (pintype "input"))
      (node (ref "IC8") (pin "10") (pinfunction "A_10") (pintype "input"))
      (node (ref "R10") (pin "1") (pinfunction "1_1") (pintype "passive"))
      (node (ref "SEL") (pin "1") (pinfunction "1_1") (pintype "passive"))
    )
    (net (code "59") (name "Net-(IC7A-B)") (class "Default")
      (node (ref "IC7") (pin "9") (pinfunction "B_9") (pintype "input"))
      (node (ref "IC8") (pin "9") (pinfunction "B_9") (pintype "input"))
      (node (ref "R11") (pin "1") (pinfunction "1_1") (pintype "passive"))
      (node (ref "SEL") (pin "2") (pinfunction "2_2") (pintype "passive"))
    )
    (net (code "60") (name "Net-(IC7A-X)") (class "Default")
      (node (ref "IC7") (pin "13") (pinfunction "X_13") (pintype "bidirectional"))
      (node (ref "IC9") (pin "5") (pinfunction "I_5") (pintype "input"))
    )
    (net (code "61") (name "Net-(IC7A-Y)") (class "Default")
      (node (ref "IC7") (pin "3") (pinfunction "Y_3") (pintype "bidirectional"))
      (node (ref "IC9") (pin "3") (pinfunction "I_3") (pintype "input"))
    )
    (net (code "62") (name "Net-(IC8A-X)") (class "Default")
      (node (ref "IC8") (pin "13") (pinfunction "X_13") (pintype "bidirectional"))
      (node (ref "IC9") (pin "9") (pinfunction "I_9") (pintype "input"))
    )
    (net (code "63") (name "Net-(IC8A-Y)") (class "Default")
      (node (ref "IC8") (pin "3") (pinfunction "Y_3") (pintype "bidirectional"))
      (node (ref "IC9") (pin "7") (pinfunction "I_7") (pintype "input"))
    )
    (net (code "64") (name "Net-(IC9A-O)") (class "Default")
      (node (ref "IC9") (pin "2") (pinfunction "O_2") (pintype "output"))
      (node (ref "LED") (pin "2") (pinfunction "2_2") (pintype "passive"))
      (node (ref "R13") (pin "1") (pinfunction "1_1") (pintype "passive"))
    )
    (net (code "65") (name "Net-(IC9B-O)") (class "Default")
      (node (ref "IC9") (pin "4") (pinfunction "O_4") (pintype "output"))
      (node (ref "LED") (pin "1") (pinfunction "1_1") (pintype "passive"))
      (node (ref "R12") (pin "1") (pinfunction "1_1") (pintype "passive"))
    )
    (net (code "66") (name "Net-(IC9C-O)") (class "Default")
      (node (ref "IC9") (pin "6") (pinfunction "O_6") (pintype "output"))
      (node (ref "LED") (pin "4") (pinfunction "4_4") (pintype "passive"))
      (node (ref "R15") (pin "1") (pinfunction "1_1") (pintype "passive"))
    )
    (net (code "67") (name "Net-(IC9D-O)") (class "Default")
      (node (ref "IC9") (pin "10") (pinfunction "O_10") (pintype "output"))
      (node (ref "LED") (pin "3") (pinfunction "3_3") (pintype "passive"))
      (node (ref "R14") (pin "1") (pinfunction "1_1") (pintype "passive"))
    )
    (net (code "68") (name "Net-(M2-Pad1)") (class "Default")
      (node (ref "M2") (pin "1") (pinfunction "1_1") (pintype "passive"))
      (node (ref "Y1") (pin "2") (pinfunction "2_2") (pintype "passive"))
    )
    (net (code "69") (name "Net-(M2-Pad2)") (class "Default")
      (node (ref "M2") (pin "2") (pinfunction "2_2") (pintype "passive"))
      (node (ref "Y2") (pin "2") (pinfunction "2_2") (pintype "passive"))
    )
    (net (code "70") (name "Net-(M2-Pad3)") (class "Default")
      (node (ref "M2") (pin "3") (pinfunction "3_3") (pintype "passive"))
      (node (ref "Y3") (pin "2") (pinfunction "2_2") (pintype "passive"))
    )
    (net (code "71") (name "Net-(M2-Pad4)") (class "Default")
      (node (ref "M2") (pin "4") (pinfunction "4_4") (pintype "passive"))
      (node (ref "Y4") (pin "2") (pinfunction "2_2") (pintype "passive"))
    )
    (net (code "72") (name "Net-(M4-Pad1)") (class "Default")
      (node (ref "M4") (pin "1") (pinfunction "1_1") (pintype "passive"))
      (node (ref "X1") (pin "2") (pinfunction "2_2") (pintype "passive"))
    )
    (net (code "73") (name "Net-(M4-Pad2)") (class "Default")
      (node (ref "M4") (pin "2") (pinfunction "2_2") (pintype "passive"))
      (node (ref "X2") (pin "2") (pinfunction "2_2") (pintype "passive"))
    )
    (net (code "74") (name "Net-(M4-Pad3)") (class "Default")
      (node (ref "M4") (pin "3") (pinfunction "3_3") (pintype "passive"))
      (node (ref "X3") (pin "2") (pinfunction "2_2") (pintype "passive"))
    )
    (net (code "75") (name "Net-(M4-Pad4)") (class "Default")
      (node (ref "M4") (pin "4") (pinfunction "4_4") (pintype "passive"))
      (node (ref "X4") (pin "2") (pinfunction "2_2") (pintype "passive"))
    )
    (net (code "76") (name "Net-(R6-Pad1)") (class "Default")
      (node (ref "R6") (pin "1") (pinfunction "1_1") (pintype "passive"))
      (node (ref "USB") (pin "1") (pinfunction "1_1") (pintype "passive"))
    )
    (net (code "77") (name "OUT1A") (class "Default")
      (node (ref "A1") (pin "1") (pinfunction "1_1") (pintype "passive"))
      (node (ref "D4") (pin "A") (pinfunction "A_A") (pintype "passive"))
      (node (ref "D8") (pin "C") (pinfunction "C_C") (pintype "passive"))
      (node (ref "IC2") (pin "7") (pinfunction "OUT1A_7") (pintype "output"))
      (node (ref "IC3") (pin "10") (pinfunction "3A_10") (pintype "input"))
      (node (ref "IC7") (pin "12") (pinfunction "X0_12") (pintype "bidirectional"))
    )
    (net (code "78") (name "OUT1B") (class "Default")
      (node (ref "B1") (pin "1") (pinfunction "1_1") (pintype "passive"))
      (node (ref "D12") (pin "A") (pinfunction "A_A") (pintype "passive"))
      (node (ref "D16") (pin "C") (pinfunction "C_C") (pintype "passive"))
      (node (ref "IC2") (pin "22") (pinfunction "OUT1B_22") (pintype "output"))
      (node (ref "IC4") (pin "10") (pinfunction "3A_10") (pintype "input"))
      (node (ref "IC7") (pin "14") (pinfunction "X1_14") (pintype "bidirectional"))
    )
    (net (code "79") (name "OUT1C") (class "Default")
      (node (ref "D30") (pin "C") (pinfunction "C_C") (pintype "passive"))
      (node (ref "D32") (pin "A") (pinfunction "A_A") (pintype "passive"))
      (node (ref "IC2") (pin "21") (pinfunction "OUT1C_21") (pintype "output"))
      (node (ref "IC6") (pin "10") (pinfunction "3A_10") (pintype "input"))
      (node (ref "IC7") (pin "15") (pinfunction "X2_15") (pintype "bidirectional"))
      (node (ref "Y1") (pin "1") (pinfunction "1_1") (pintype "passive"))
    )
    (net (code "80") (name "OUT1D") (class "Default")
      (node (ref "D20") (pin "A") (pinfunction "A_A") (pintype "passive"))
      (node (ref "D24") (pin "C") (pinfunction "C_C") (pintype "passive"))
      (node (ref "IC2") (pin "8") (pinfunction "OUT1D_8") (pintype "output"))
      (node (ref "IC5") (pin "10") (pinfunction "3A_10") (pintype "input"))
      (node (ref "IC7") (pin "11") (pinfunction "X3_11") (pintype "bidirectional"))
      (node (ref "X1") (pin "1") (pinfunction "1_1") (pintype "passive"))
    )
    (net (code "81") (name "OUT2A") (class "Default")
      (node (ref "A2") (pin "1") (pinfunction "1_1") (pintype "passive"))
      (node (ref "D3") (pin "A") (pinfunction "A_A") (pintype "passive"))
      (node (ref "D7") (pin "C") (pinfunction "C_C") (pintype "passive"))
      (node (ref "IC2") (pin "6") (pinfunction "OUT2A_6") (pintype "output"))
      (node (ref "IC3") (pin "15") (pinfunction "4A_15") (pintype "input"))
      (node (ref "IC7") (pin "1") (pinfunction "Y0_1") (pintype "bidirectional"))
    )
    (net (code "82") (name "OUT2B") (class "Default")
      (node (ref "B2") (pin "1") (pinfunction "1_1") (pintype "passive"))
      (node (ref "D11") (pin "A") (pinfunction "A_A") (pintype "passive"))
      (node (ref "D15") (pin "C") (pinfunction "C_C") (pintype "passive"))
      (node (ref "IC2") (pin "23") (pinfunction "OUT2B_23") (pintype "output"))
      (node (ref "IC4") (pin "15") (pinfunction "4A_15") (pintype "input"))
      (node (ref "IC7") (pin "5") (pinfunction "Y1_5") (pintype "bidirectional"))
    )
    (net (code "83") (name "OUT2C") (class "Default")
      (node (ref "D29") (pin "C") (pinfunction "C_C") (pintype "passive"))
      (node (ref "D31") (pin "A") (pinfunction "A_A") (pintype "passive"))
      (node (ref "IC2") (pin "20") (pinfunction "OUT2C_20") (pintype "output"))
      (node (ref "IC6") (pin "15") (pinfunction "4A_15") (pintype "input"))
      (node (ref "IC7") (pin "2") (pinfunction "Y2_2") (pintype "bidirectional"))
      (node (ref "Y2") (pin "1") (pinfunction "1_1") (pintype "passive"))
    )
    (net (code "84") (name "OUT2D") (class "Default")
      (node (ref "D19") (pin "A") (pinfunction "A_A") (pintype "passive"))
      (node (ref "D23") (pin "C") (pinfunction "C_C") (pintype "passive"))
      (node (ref "IC2") (pin "9") (pinfunction "OUT2D_9") (pintype "output"))
      (node (ref "IC5") (pin "15") (pinfunction "4A_15") (pintype "input"))
      (node (ref "IC7") (pin "4") (pinfunction "Y3_4") (pintype "bidirectional"))
      (node (ref "X2") (pin "1") (pinfunction "1_1") (pintype "passive"))
    )
    (net (code "85") (name "OUT3A") (class "Default")
      (node (ref "A3") (pin "1") (pinfunction "1_1") (pintype "passive"))
      (node (ref "D1") (pin "A") (pinfunction "A_A") (pintype "passive"))
      (node (ref "D5") (pin "C") (pinfunction "C_C") (pintype "passive"))
      (node (ref "IC2") (pin "4") (pinfunction "OUT3A_4") (pintype "output"))
      (node (ref "IC3") (pin "7") (pinfunction "2A_7") (pintype "input"))
      (node (ref "IC8") (pin "12") (pinfunction "X0_12") (pintype "bidirectional"))
    )
    (net (code "86") (name "OUT3B") (class "Default")
      (node (ref "B3") (pin "1") (pinfunction "1_1") (pintype "passive"))
      (node (ref "D13") (pin "C") (pinfunction "C_C") (pintype "passive"))
      (node (ref "D9") (pin "A") (pinfunction "A_A") (pintype "passive"))
      (node (ref "IC2") (pin "25") (pinfunction "OUT3B_25") (pintype "output"))
      (node (ref "IC4") (pin "2") (pinfunction "1A_2") (pintype "input"))
      (node (ref "IC8") (pin "14") (pinfunction "X1_14") (pintype "bidirectional"))
    )
    (net (code "87") (name "OUT3C") (class "Default")
      (node (ref "D25") (pin "A") (pinfunction "A_A") (pintype "passive"))
      (node (ref "D28") (pin "C") (pinfunction "C_C") (pintype "passive"))
      (node (ref "IC2") (pin "18") (pinfunction "OUT3C_18") (pintype "output"))
      (node (ref "IC6") (pin "2") (pinfunction "1A_2") (pintype "input"))
      (node (ref "IC8") (pin "15") (pinfunction "X2_15") (pintype "bidirectional"))
      (node (ref "Y3") (pin "1") (pinfunction "1_1") (pintype "passive"))
    )
    (net (code "88") (name "OUT3D") (class "Default")
      (node (ref "D17") (pin "A") (pinfunction "A_A") (pintype "passive"))
      (node (ref "D21") (pin "C") (pinfunction "C_C") (pintype "passive"))
      (node (ref "IC2") (pin "11") (pinfunction "OUT3D_11") (pintype "output"))
      (node (ref "IC5") (pin "2") (pinfunction "1A_2") (pintype "input"))
      (node (ref "IC8") (pin "11") (pinfunction "X3_11") (pintype "bidirectional"))
      (node (ref "X3") (pin "1") (pinfunction "1_1") (pintype "passive"))
    )
    (net (code "89") (name "OUT4A") (class "Default")
      (node (ref "A4") (pin "1") (pinfunction "1_1") (pintype "passive"))
      (node (ref "D2") (pin "A") (pinfunction "A_A") (pintype "passive"))
      (node (ref "D6") (pin "C") (pinfunction "C_C") (pintype "passive"))
      (node (ref "IC2") (pin "5") (pinfunction "OUT4A_5") (pintype "output"))
      (node (ref "IC3") (pin "2") (pinfunction "1A_2") (pintype "input"))
      (node (ref "IC8") (pin "1") (pinfunction "Y0_1") (pintype "bidirectional"))
    )
    (net (code "90") (name "OUT4B") (class "Default")
      (node (ref "B4") (pin "1") (pinfunction "1_1") (pintype "passive"))
      (node (ref "D10") (pin "A") (pinfunction "A_A") (pintype "passive"))
      (node (ref "D14") (pin "C") (pinfunction "C_C") (pintype "passive"))
      (node (ref "IC2") (pin "24") (pinfunction "OUT4B_24") (pintype "output"))
      (node (ref "IC4") (pin "7") (pinfunction "2A_7") (pintype "input"))
      (node (ref "IC8") (pin "5") (pinfunction "Y1_5") (pintype "bidirectional"))
    )
    (net (code "91") (name "OUT4C") (class "Default")
      (node (ref "D26") (pin "A") (pinfunction "A_A") (pintype "passive"))
      (node (ref "D27") (pin "C") (pinfunction "C_C") (pintype "passive"))
      (node (ref "IC2") (pin "19") (pinfunction "OUT4C_19") (pintype "output"))
      (node (ref "IC6") (pin "7") (pinfunction "2A_7") (pintype "input"))
      (node (ref "IC8") (pin "2") (pinfunction "Y2_2") (pintype "bidirectional"))
      (node (ref "Y4") (pin "1") (pinfunction "1_1") (pintype "passive"))
    )
    (net (code "92") (name "OUT4D") (class "Default")
      (node (ref "D18") (pin "A") (pinfunction "A_A") (pintype "passive"))
      (node (ref "D22") (pin "C") (pinfunction "C_C") (pintype "passive"))
      (node (ref "IC2") (pin "10") (pinfunction "OUT4D_10") (pintype "output"))
      (node (ref "IC5") (pin "7") (pinfunction "2A_7") (pintype "input"))
      (node (ref "IC8") (pin "4") (pinfunction "Y3_4") (pintype "bidirectional"))
      (node (ref "X4") (pin "1") (pinfunction "1_1") (pintype "passive"))
    )
    (net (code "93") (name "RST") (class "Default")
      (node (ref "IC1") (pin "26") (pinfunction "RB5/KBI1/PGM_26") (pintype "bidirectional"))
      (node (ref "IC2") (pin "26") (pinfunction "~{RST}_26") (pintype "input"))
    )
    (net (code "94") (name "VM") (class "Default")
      (node (ref "C7") (pin "+") (pinfunction "+_+") (pintype "passive"))
      (node (ref "IC3") (pin "16") (pinfunction "VCC1_16") (pintype "power_in"))
      (node (ref "IC3") (pin "8") (pinfunction "VCC2_8") (pintype "power_in"))
      (node (ref "IC4") (pin "16") (pinfunction "VCC1_16") (pintype "power_in"))
      (node (ref "IC4") (pin "8") (pinfunction "VCC2_8") (pintype "power_in"))
      (node (ref "IC5") (pin "16") (pinfunction "VCC1_16") (pintype "power_in"))
      (node (ref "IC5") (pin "8") (pinfunction "VCC2_8") (pintype "power_in"))
      (node (ref "IC6") (pin "16") (pinfunction "VCC1_16") (pintype "power_in"))
      (node (ref "IC6") (pin "8") (pinfunction "VCC2_8") (pintype "power_in"))
      (node (ref "MOTPWR") (pin "2") (pinfunction "2_2") (pintype "passive"))
    )
    (net (code "95") (name "VMOT") (class "Default")
      (node (ref "MOTPWR") (pin "3") (pinfunction "3_3") (pintype "passive"))
      (node (ref "POWER") (pin "3") (pinfunction "3_3") (pintype "passive"))
    )
    (net (code "96") (name "unconnected-(IC9E-O-Pad12)") (class "Default")
      (node (ref "IC9") (pin "12") (pinfunction "O_12") (pintype "output"))
    )
    (net (code "97") (name "unconnected-(IC9F-O-Pad15)") (class "Default")
      (node (ref "IC9") (pin "15") (pinfunction "O_15") (pintype "output"))
    )
  )
)
